# BaseBoard.net
KiCad netlist of a schematic drawn in EAGLE
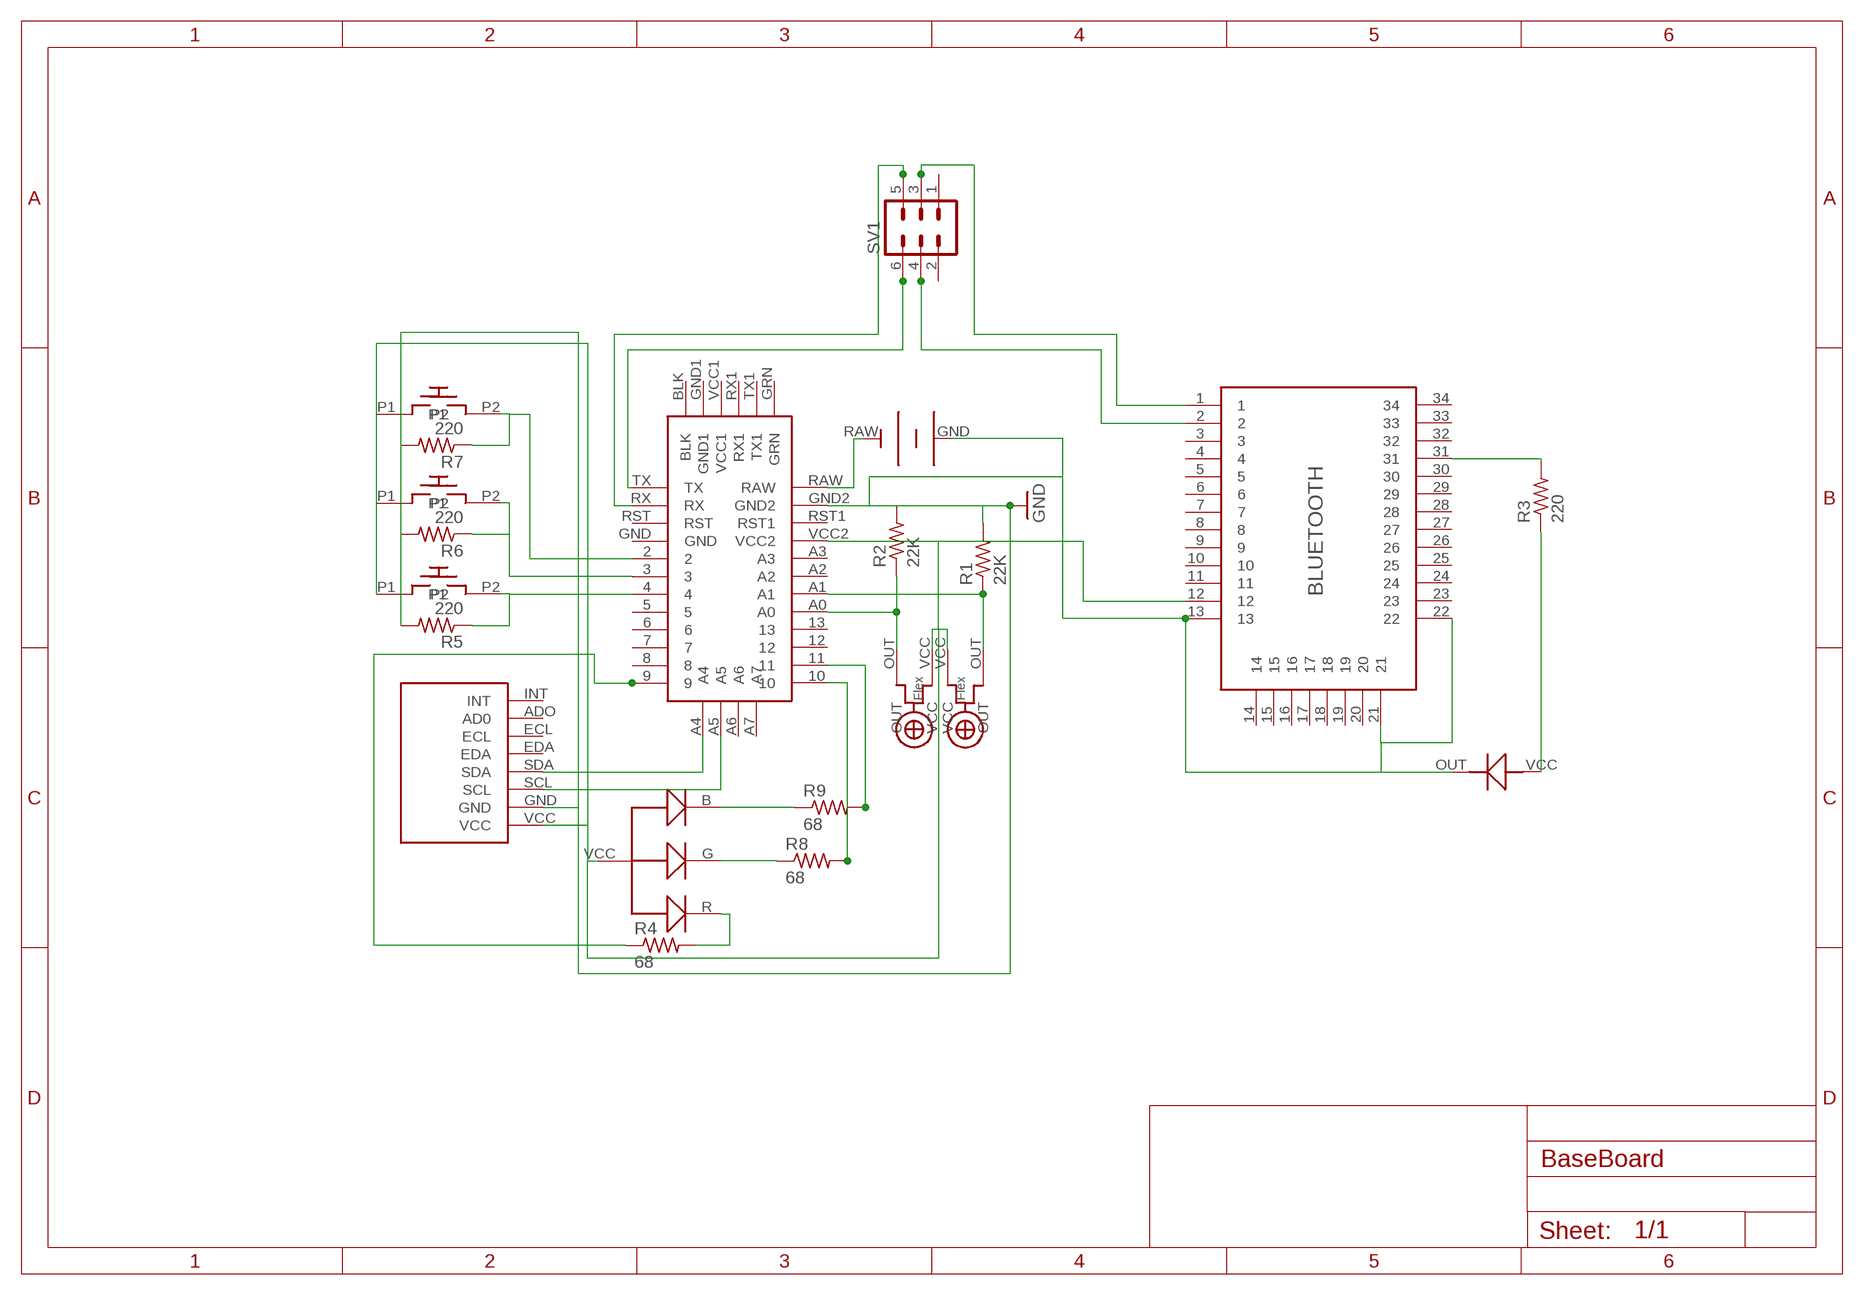
[diagram p0: schematic, sheet 1]

(export (version "E")
  (design (tool "Eeschema 10.0.6"))
  (components
    (comp (ref "BLUETOOTH-LED")
      (value "LED")
      (footprint "eagle-import:FLEX")
      (libsource (lib "eagle-import") (part "LED"))
    )
    (comp (ref "R1")
      (value "22K")
      (footprint "eagle-import:R1206")
      (libsource (lib "eagle-import") (part "R-US_R1206"))
    )
    (comp (ref "R2")
      (value "22K")
      (footprint "eagle-import:R1206")
      (libsource (lib "eagle-import") (part "R-US_R1206"))
    )
    (comp (ref "R3")
      (value "220")
      (footprint "eagle-import:R1206")
      (libsource (lib "eagle-import") (part "R-US_R1206"))
    )
    (comp (ref "R4")
      (value "68")
      (footprint "eagle-import:R1206")
      (libsource (lib "eagle-import") (part "R-US_R1206"))
    )
    (comp (ref "R5")
      (value "220")
      (footprint "eagle-import:R1206")
      (libsource (lib "eagle-import") (part "R-US_R1206"))
    )
    (comp (ref "R6")
      (value "220")
      (footprint "eagle-import:R1206")
      (libsource (lib "eagle-import") (part "R-US_R1206"))
    )
    (comp (ref "R7")
      (value "220")
      (footprint "eagle-import:R1206")
      (libsource (lib "eagle-import") (part "R-US_R1206"))
    )
    (comp (ref "R8")
      (value "68")
      (footprint "eagle-import:R1206")
      (libsource (lib "eagle-import") (part "R-US_R1206"))
    )
    (comp (ref "R9")
      (value "68")
      (footprint "eagle-import:R1206")
      (libsource (lib "eagle-import") (part "R-US_R1206"))
    )
    (comp (ref "SV1")
      (value "MA03-2")
      (footprint "eagle-import:MA03-2")
      (libsource (lib "eagle-import") (part "MA03-2"))
    )
    (comp (ref "TOGGEL")
      (value "PB")
      (footprint "eagle-import:PB")
      (libsource (lib "eagle-import") (part "PB"))
    )
    (comp (ref "U$1")
      (value "APM")
      (footprint "eagle-import:APM")
      (libsource (lib "eagle-import") (part "APM"))
    )
    (comp (ref "U$2")
      (value "MPU-9150")
      (footprint "eagle-import:MPU-9150")
      (libsource (lib "eagle-import") (part "MPU-9150"))
    )
    (comp (ref "U$3")
      (value "FLEX")
      (footprint "eagle-import:FLEX")
      (libsource (lib "eagle-import") (part "FLEX"))
    )
    (comp (ref "U$4")
      (value "FLEX")
      (footprint "eagle-import:FLEX")
      (libsource (lib "eagle-import") (part "FLEX"))
    )
    (comp (ref "U$5")
      (value "BATT")
      (footprint "eagle-import:BAT")
      (libsource (lib "eagle-import") (part "BATT"))
    )
    (comp (ref "U$6")
      (value "BLUETOOTH")
      (footprint "eagle-import:BLUETOOTH")
      (libsource (lib "eagle-import") (part "BLUETOOTH"))
    )
    (comp (ref "U$7")
      (value "LED-RGB")
      (footprint "eagle-import:LED")
      (libsource (lib "eagle-import") (part "LED-RGB"))
    )
    (comp (ref "U$9") (value "PB") (footprint "eagle-import:PB") (libsource (lib "eagle-import") (part "PB")))
    (comp (ref "U$10")
      (value "PB")
      (footprint "eagle-import:PB")
      (libsource (lib "eagle-import") (part "PB"))
    )
  )
  (nets
    (net (code "1") (name "GND") (class "Default")
      (node (ref "BLUETOOTH-LED") (pin "OUT") (pinfunction "1_OUT") (pintype "bidirectional"))
      (node (ref "R1") (pin "2") (pinfunction "2_2") (pintype "passive"))
      (node (ref "R2") (pin "2") (pinfunction "2_2") (pintype "passive"))
      (node (ref "R5") (pin "2") (pinfunction "2_2") (pintype "passive"))
      (node (ref "R6") (pin "2") (pinfunction "2_2") (pintype "passive"))
      (node (ref "R7") (pin "2") (pinfunction "2_2") (pintype "passive"))
      (node (ref "U$1") (pin "GND2") (pinfunction "GND2_GND2") (pintype "bidirectional"))
      (node (ref "U$2") (pin "GND") (pinfunction "GND_GND") (pintype "bidirectional"))
      (node (ref "U$5") (pin "GND") (pinfunction "GND_GND") (pintype "bidirectional"))
      (node (ref "U$6") (pin "13") (pinfunction "13_13") (pintype "bidirectional"))
      (node (ref "U$6") (pin "21") (pinfunction "21_21") (pintype "bidirectional"))
      (node (ref "U$6") (pin "22") (pinfunction "22_22") (pintype "bidirectional"))
    )
    (net (code "2") (name "Net-(BLUETOOTH-LED-2)") (class "Default")
      (node (ref "BLUETOOTH-LED") (pin "VCC") (pinfunction "2_VCC") (pintype "bidirectional"))
      (node (ref "R3") (pin "1") (pinfunction "1_1") (pintype "passive"))
    )
    (net (code "3") (name "Net-(R1-Pad1)") (class "Default")
      (node (ref "R1") (pin "1") (pinfunction "1_1") (pintype "passive"))
      (node (ref "U$1") (pin "A1") (pinfunction "A1_A1") (pintype "bidirectional"))
      (node (ref "U$4") (pin "OUT") (pinfunction "OUT_OUT") (pintype "bidirectional"))
    )
    (net (code "4") (name "Net-(R2-Pad1)") (class "Default")
      (node (ref "R2") (pin "1") (pinfunction "1_1") (pintype "passive"))
      (node (ref "U$1") (pin "A0") (pinfunction "A0_A0") (pintype "bidirectional"))
      (node (ref "U$3") (pin "OUT") (pinfunction "OUT_OUT") (pintype "bidirectional"))
    )
    (net (code "5") (name "Net-(R3-Pad2)") (class "Default")
      (node (ref "R3") (pin "2") (pinfunction "2_2") (pintype "passive"))
      (node (ref "U$6") (pin "31") (pinfunction "31_31") (pintype "bidirectional"))
    )
    (net (code "6") (name "Net-(R4-Pad1)") (class "Default")
      (node (ref "R4") (pin "1") (pinfunction "1_1") (pintype "passive"))
      (node (ref "U$1") (pin "9") (pinfunction "9_9") (pintype "bidirectional"))
    )
    (net (code "7") (name "Net-(R4-Pad2)") (class "Default")
      (node (ref "R4") (pin "2") (pinfunction "2_2") (pintype "passive"))
      (node (ref "U$7") (pin "R") (pinfunction "R_R") (pintype "bidirectional"))
    )
    (net (code "8") (name "Net-(R5-Pad1)") (class "Default")
      (node (ref "R5") (pin "1") (pinfunction "1_1") (pintype "passive"))
      (node (ref "TOGGEL") (pin "P2") (pinfunction "P2_P2") (pintype "bidirectional"))
      (node (ref "U$1") (pin "4") (pinfunction "4_4") (pintype "bidirectional"))
    )
    (net (code "9") (name "Net-(R6-Pad1)") (class "Default")
      (node (ref "R6") (pin "1") (pinfunction "1_1") (pintype "passive"))
      (node (ref "U$1") (pin "3") (pinfunction "3_3") (pintype "bidirectional"))
      (node (ref "U$9") (pin "P2") (pinfunction "P2_P2") (pintype "bidirectional"))
    )
    (net (code "10") (name "Net-(R7-Pad1)") (class "Default")
      (node (ref "R7") (pin "1") (pinfunction "1_1") (pintype "passive"))
      (node (ref "U$1") (pin "2") (pinfunction "2_2") (pintype "bidirectional"))
      (node (ref "U$10") (pin "P2") (pinfunction "P2_P2") (pintype "bidirectional"))
    )
    (net (code "11") (name "Net-(R8-Pad1)") (class "Default")
      (node (ref "R8") (pin "1") (pinfunction "1_1") (pintype "passive"))
      (node (ref "U$7") (pin "G") (pinfunction "G_G") (pintype "bidirectional"))
    )
    (net (code "12") (name "Net-(R8-Pad2)") (class "Default")
      (node (ref "R8") (pin "2") (pinfunction "2_2") (pintype "passive"))
      (node (ref "U$1") (pin "10") (pinfunction "10_10") (pintype "bidirectional"))
    )
    (net (code "13") (name "Net-(R9-Pad1)") (class "Default")
      (node (ref "R9") (pin "1") (pinfunction "1_1") (pintype "passive"))
      (node (ref "U$7") (pin "B") (pinfunction "B_B") (pintype "bidirectional"))
    )
    (net (code "14") (name "Net-(R9-Pad2)") (class "Default")
      (node (ref "R9") (pin "2") (pinfunction "2_2") (pintype "passive"))
      (node (ref "U$1") (pin "11") (pinfunction "11_11") (pintype "bidirectional"))
    )
    (net (code "15") (name "Net-(SV1-Pad3)") (class "Default")
      (node (ref "SV1") (pin "3") (pinfunction "3_3") (pintype "passive"))
      (node (ref "U$6") (pin "1") (pinfunction "1_1") (pintype "bidirectional"))
    )
    (net (code "16") (name "Net-(SV1-Pad4)") (class "Default")
      (node (ref "SV1") (pin "4") (pinfunction "4_4") (pintype "passive"))
      (node (ref "U$6") (pin "2") (pinfunction "2_2") (pintype "bidirectional"))
    )
    (net (code "17") (name "Net-(SV1-Pad5)") (class "Default")
      (node (ref "SV1") (pin "5") (pinfunction "5_5") (pintype "passive"))
      (node (ref "U$1") (pin "RX") (pinfunction "RX_RX") (pintype "bidirectional"))
    )
    (net (code "18") (name "Net-(SV1-Pad6)") (class "Default")
      (node (ref "SV1") (pin "6") (pinfunction "6_6") (pintype "passive"))
      (node (ref "U$1") (pin "TX") (pinfunction "TX_TX") (pintype "bidirectional"))
    )
    (net (code "19") (name "Net-(TOGGEL-PadP1)") (class "Default")
      (node (ref "TOGGEL") (pin "P1") (pinfunction "P1_P1") (pintype "bidirectional"))
      (node (ref "U$1") (pin "VCC2") (pinfunction "VCC2_VCC2") (pintype "bidirectional"))
      (node (ref "U$10") (pin "P1") (pinfunction "P1_P1") (pintype "bidirectional"))
      (node (ref "U$2") (pin "VCC") (pinfunction "VCC_VCC") (pintype "bidirectional"))
      (node (ref "U$3") (pin "VCC") (pinfunction "VCC_VCC") (pintype "bidirectional"))
      (node (ref "U$4") (pin "VCC") (pinfunction "VCC_VCC") (pintype "bidirectional"))
      (node (ref "U$6") (pin "12") (pinfunction "12_12") (pintype "bidirectional"))
      (node (ref "U$7") (pin "VCC") (pinfunction "VCC_VCC") (pintype "bidirectional"))
      (node (ref "U$9") (pin "P1") (pinfunction "P1_P1") (pintype "bidirectional"))
    )
    (net (code "20") (name "Net-(U$1-PadA4)") (class "Default")
      (node (ref "U$1") (pin "A4") (pinfunction "A4_A4") (pintype "bidirectional"))
      (node (ref "U$2") (pin "SDA") (pinfunction "SDA_SDA") (pintype "bidirectional"))
    )
    (net (code "21") (name "Net-(U$1-PadA5)") (class "Default")
      (node (ref "U$1") (pin "A5") (pinfunction "A5_A5") (pintype "bidirectional"))
      (node (ref "U$2") (pin "SCL") (pinfunction "SCL_SCL") (pintype "bidirectional"))
    )
    (net (code "22") (name "Net-(U$1-PadRAW)") (class "Default")
      (node (ref "U$1") (pin "RAW") (pinfunction "RAW_RAW") (pintype "bidirectional"))
      (node (ref "U$5") (pin "RAW") (pinfunction "RAW_RAW") (pintype "bidirectional"))
    )
    (net (code "23") (name "unconnected-(SV1-Pad1)") (class "Default")
      (node (ref "SV1") (pin "1") (pinfunction "1_1") (pintype "passive"))
    )
    (net (code "24") (name "unconnected-(SV1-Pad2)") (class "Default")
      (node (ref "SV1") (pin "2") (pinfunction "2_2") (pintype "passive"))
    )
    (net (code "25") (name "unconnected-(U$1-Pad5)") (class "Default")
      (node (ref "U$1") (pin "5") (pinfunction "5_5") (pintype "bidirectional"))
    )
    (net (code "26") (name "unconnected-(U$1-Pad6)") (class "Default")
      (node (ref "U$1") (pin "6") (pinfunction "6_6") (pintype "bidirectional"))
    )
    (net (code "27") (name "unconnected-(U$1-Pad7)") (class "Default")
      (node (ref "U$1") (pin "7") (pinfunction "7_7") (pintype "bidirectional"))
    )
    (net (code "28") (name "unconnected-(U$1-Pad8)") (class "Default")
      (node (ref "U$1") (pin "8") (pinfunction "8_8") (pintype "bidirectional"))
    )
    (net (code "29") (name "unconnected-(U$1-Pad12)") (class "Default")
      (node (ref "U$1") (pin "12") (pinfunction "12_12") (pintype "bidirectional"))
    )
    (net (code "30") (name "unconnected-(U$1-Pad13)") (class "Default")
      (node (ref "U$1") (pin "13") (pinfunction "13_13") (pintype "bidirectional"))
    )
    (net (code "31") (name "unconnected-(U$1-PadA2)") (class "Default")
      (node (ref "U$1") (pin "A2") (pinfunction "A2_A2") (pintype "bidirectional"))
    )
    (net (code "32") (name "unconnected-(U$1-PadA3)") (class "Default")
      (node (ref "U$1") (pin "A3") (pinfunction "A3_A3") (pintype "bidirectional"))
    )
    (net (code "33") (name "unconnected-(U$1-PadA6)") (class "Default")
      (node (ref "U$1") (pin "A6") (pinfunction "A6_A6") (pintype "bidirectional"))
    )
    (net (code "34") (name "unconnected-(U$1-PadA7)") (class "Default")
      (node (ref "U$1") (pin "A7") (pinfunction "A7_A7") (pintype "bidirectional"))
    )
    (net (code "35") (name "unconnected-(U$1-PadBLK)") (class "Default")
      (node (ref "U$1") (pin "BLK") (pinfunction "BLK_BLK") (pintype "bidirectional"))
    )
    (net (code "36") (name "unconnected-(U$1-PadGND)") (class "Default")
      (node (ref "U$1") (pin "GND") (pinfunction "GND_GND") (pintype "bidirectional"))
    )
    (net (code "37") (name "unconnected-(U$1-PadGND1)") (class "Default")
      (node (ref "U$1") (pin "GND1") (pinfunction "GND1_GND1") (pintype "bidirectional"))
    )
    (net (code "38") (name "unconnected-(U$1-PadGRN)") (class "Default")
      (node (ref "U$1") (pin "GRN") (pinfunction "GRN_GRN") (pintype "bidirectional"))
    )
    (net (code "39") (name "unconnected-(U$1-PadRST)") (class "Default")
      (node (ref "U$1") (pin "RST") (pinfunction "RST_RST") (pintype "bidirectional"))
    )
    (net (code "40") (name "unconnected-(U$1-PadRST1)") (class "Default")
      (node (ref "U$1") (pin "RST1") (pinfunction "RST1_RST1") (pintype "bidirectional"))
    )
    (net (code "41") (name "unconnected-(U$1-PadRX1)") (class "Default")
      (node (ref "U$1") (pin "RX1") (pinfunction "RX1_RX1") (pintype "bidirectional"))
    )
    (net (code "42") (name "unconnected-(U$1-PadTX1)") (class "Default")
      (node (ref "U$1") (pin "TX1") (pinfunction "TX1_TX1") (pintype "bidirectional"))
    )
    (net (code "43") (name "unconnected-(U$1-PadVCC1)") (class "Default")
      (node (ref "U$1") (pin "VCC1") (pinfunction "VCC1_VCC1") (pintype "bidirectional"))
    )
    (net (code "44") (name "unconnected-(U$2-AD0-PadADO)") (class "Default")
      (node (ref "U$2") (pin "ADO") (pinfunction "AD0_ADO") (pintype "bidirectional"))
    )
    (net (code "45") (name "unconnected-(U$2-PadECL)") (class "Default")
      (node (ref "U$2") (pin "ECL") (pinfunction "ECL_ECL") (pintype "bidirectional"))
    )
    (net (code "46") (name "unconnected-(U$2-PadEDA)") (class "Default")
      (node (ref "U$2") (pin "EDA") (pinfunction "EDA_EDA") (pintype "bidirectional"))
    )
    (net (code "47") (name "unconnected-(U$2-PadINT)") (class "Default")
      (node (ref "U$2") (pin "INT") (pinfunction "INT_INT") (pintype "bidirectional"))
    )
    (net (code "48") (name "unconnected-(U$6-Pad3)") (class "Default")
      (node (ref "U$6") (pin "3") (pinfunction "3_3") (pintype "bidirectional"))
    )
    (net (code "49") (name "unconnected-(U$6-Pad4)") (class "Default")
      (node (ref "U$6") (pin "4") (pinfunction "4_4") (pintype "bidirectional"))
    )
    (net (code "50") (name "unconnected-(U$6-Pad5)") (class "Default")
      (node (ref "U$6") (pin "5") (pinfunction "5_5") (pintype "bidirectional"))
    )
    (net (code "51") (name "unconnected-(U$6-Pad6)") (class "Default")
      (node (ref "U$6") (pin "6") (pinfunction "6_6") (pintype "bidirectional"))
    )
    (net (code "52") (name "unconnected-(U$6-Pad7)") (class "Default")
      (node (ref "U$6") (pin "7") (pinfunction "7_7") (pintype "bidirectional"))
    )
    (net (code "53") (name "unconnected-(U$6-Pad8)") (class "Default")
      (node (ref "U$6") (pin "8") (pinfunction "8_8") (pintype "bidirectional"))
    )
    (net (code "54") (name "unconnected-(U$6-Pad9)") (class "Default")
      (node (ref "U$6") (pin "9") (pinfunction "9_9") (pintype "bidirectional"))
    )
    (net (code "55") (name "unconnected-(U$6-Pad10)") (class "Default")
      (node (ref "U$6") (pin "10") (pinfunction "10_10") (pintype "bidirectional"))
    )
    (net (code "56") (name "unconnected-(U$6-Pad11)") (class "Default")
      (node (ref "U$6") (pin "11") (pinfunction "11_11") (pintype "bidirectional"))
    )
    (net (code "57") (name "unconnected-(U$6-Pad14)") (class "Default")
      (node (ref "U$6") (pin "14") (pinfunction "14_14") (pintype "bidirectional"))
    )
    (net (code "58") (name "unconnected-(U$6-Pad15)") (class "Default")
      (node (ref "U$6") (pin "15") (pinfunction "15_15") (pintype "bidirectional"))
    )
    (net (code "59") (name "unconnected-(U$6-Pad16)") (class "Default")
      (node (ref "U$6") (pin "16") (pinfunction "16_16") (pintype "bidirectional"))
    )
    (net (code "60") (name "unconnected-(U$6-Pad17)") (class "Default")
      (node (ref "U$6") (pin "17") (pinfunction "17_17") (pintype "bidirectional"))
    )
    (net (code "61") (name "unconnected-(U$6-Pad18)") (class "Default")
      (node (ref "U$6") (pin "18") (pinfunction "18_18") (pintype "bidirectional"))
    )
    (net (code "62") (name "unconnected-(U$6-Pad19)") (class "Default")
      (node (ref "U$6") (pin "19") (pinfunction "19_19") (pintype "bidirectional"))
    )
    (net (code "63") (name "unconnected-(U$6-Pad20)") (class "Default")
      (node (ref "U$6") (pin "20") (pinfunction "20_20") (pintype "bidirectional"))
    )
    (net (code "64") (name "unconnected-(U$6-Pad23)") (class "Default")
      (node (ref "U$6") (pin "23") (pinfunction "23_23") (pintype "bidirectional"))
    )
    (net (code "65") (name "unconnected-(U$6-Pad24)") (class "Default")
      (node (ref "U$6") (pin "24") (pinfunction "24_24") (pintype "bidirectional"))
    )
    (net (code "66") (name "unconnected-(U$6-Pad25)") (class "Default")
      (node (ref "U$6") (pin "25") (pinfunction "25_25") (pintype "bidirectional"))
    )
    (net (code "67") (name "unconnected-(U$6-Pad26)") (class "Default")
      (node (ref "U$6") (pin "26") (pinfunction "26_26") (pintype "bidirectional"))
    )
    (net (code "68") (name "unconnected-(U$6-Pad27)") (class "Default")
      (node (ref "U$6") (pin "27") (pinfunction "27_27") (pintype "bidirectional"))
    )
    (net (code "69") (name "unconnected-(U$6-Pad28)") (class "Default")
      (node (ref "U$6") (pin "28") (pinfunction "28_28") (pintype "bidirectional"))
    )
    (net (code "70") (name "unconnected-(U$6-Pad29)") (class "Default")
      (node (ref "U$6") (pin "29") (pinfunction "29_29") (pintype "bidirectional"))
    )
    (net (code "71") (name "unconnected-(U$6-Pad30)") (class "Default")
      (node (ref "U$6") (pin "30") (pinfunction "30_30") (pintype "bidirectional"))
    )
    (net (code "72") (name "unconnected-(U$6-Pad32)") (class "Default")
      (node (ref "U$6") (pin "32") (pinfunction "32_32") (pintype "bidirectional"))
    )
    (net (code "73") (name "unconnected-(U$6-Pad33)") (class "Default")
      (node (ref "U$6") (pin "33") (pinfunction "33_33") (pintype "bidirectional"))
    )
    (net (code "74") (name "unconnected-(U$6-Pad34)") (class "Default")
      (node (ref "U$6") (pin "34") (pinfunction "34_34") (pintype "bidirectional"))
    )
  )
)
